# CON_HOSTJTAG_10WBOXHDRRAM_VERT.net
KiCad netlist of a schematic drawn in Altium Designer
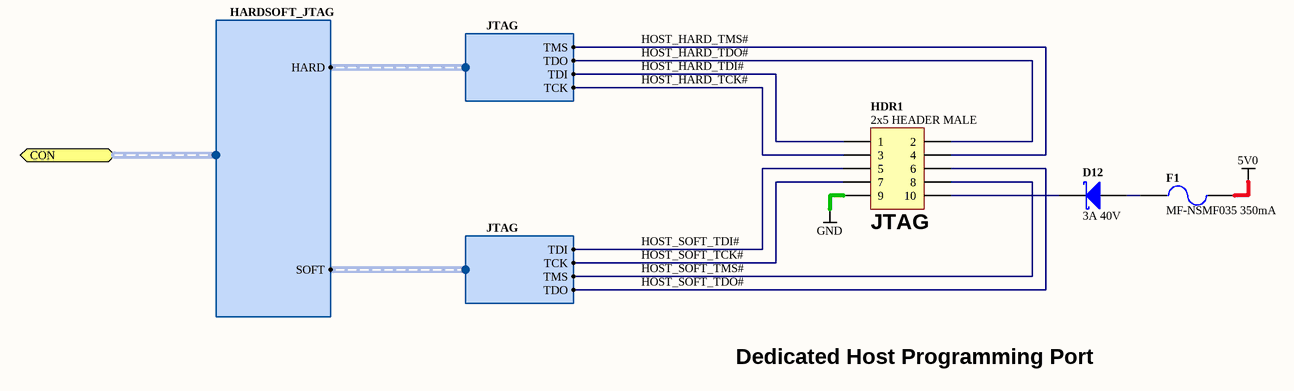
[diagram p0: CON_HOSTJTAG_10WBOXHDRRAM_VERT.SchDoc]

(export (version "E")
  (design (tool "Eeschema 10.0.6"))
  (components
    (comp (ref "D12")
      (value "3A 40V")
      (footprint "DIOM5027")
      (description "Schottky Diode, 3A 40V")
      (libsource (lib "altium-import") (part "root_2_DIO-SCHOTTKY-1S_"))
    )
    (comp (ref "F1")
      (value "MF-NSMF035 350mA")
      (footprint "RESC3216")
      (description "Multifuse, SMD 1206, 350mA")
      (libsource (lib "AltiumDesignLibrary") (part "MULTIFUSE"))
    )
    (comp (ref "HDR1")
      (value "2x5 HEADER MALE")
      (footprint "HDR2X5V")
      (description "Header IDC, 2 x 5 Pin Vertical, extended pins")
      (libsource (lib "AltiumDesignLibrary") (part "CON-IDC-2x5-M"))
    )
  )
  (nets
    (net (code "4") (name "/HOST_HARD_TCK#") (class "Default")
      (node (ref "HDR1") (pin "3") (pinfunction "3_3") (pintype "passive"))
    )
    (net (code "5") (name "/HOST_HARD_TDI#") (class "Default")
      (node (ref "HDR1") (pin "1") (pinfunction "1_1") (pintype "passive"))
    )
    (net (code "6") (name "/HOST_HARD_TDO#") (class "Default")
      (node (ref "HDR1") (pin "2") (pinfunction "2_2") (pintype "passive"))
    )
    (net (code "7") (name "/HOST_HARD_TMS#") (class "Default")
      (node (ref "HDR1") (pin "4") (pinfunction "4_4") (pintype "passive"))
    )
    (net (code "8") (name "/HOST_SOFT_TCK#") (class "Default")
      (node (ref "HDR1") (pin "7") (pinfunction "7_7") (pintype "passive"))
    )
    (net (code "9") (name "/HOST_SOFT_TDI#") (class "Default")
      (node (ref "HDR1") (pin "5") (pinfunction "5_5") (pintype "passive"))
    )
    (net (code "10") (name "/HOST_SOFT_TDO#") (class "Default")
      (node (ref "HDR1") (pin "6") (pinfunction "6_6") (pintype "passive"))
    )
    (net (code "11") (name "/HOST_SOFT_TMS#") (class "Default")
      (node (ref "HDR1") (pin "8") (pinfunction "8_8") (pintype "passive"))
    )
    (net (code "13") (name "5V0") (class "Default")
      (node (ref "F1") (pin "2") (pinfunction "2_2") (pintype "passive"))
    )
    (net (code "14") (name "GND") (class "Default")
      (node (ref "HDR1") (pin "9") (pinfunction "9_9") (pintype "passive"))
    )
    (net (code "15") (name "Net-(D12-A)") (class "Default")
      (node (ref "D12") (pin "1") (pinfunction "A_1") (pintype "passive"))
      (node (ref "F1") (pin "1") (pinfunction "1_1") (pintype "passive"))
    )
    (net (code "16") (name "Net-(D12-K)") (class "Default")
      (node (ref "D12") (pin "2") (pinfunction "K_2") (pintype "passive"))
      (node (ref "HDR1") (pin "10") (pinfunction "10_10") (pintype "passive"))
    )
  )
)
